# main.net
KiCad netlist of a schematic drawn in EAGLE
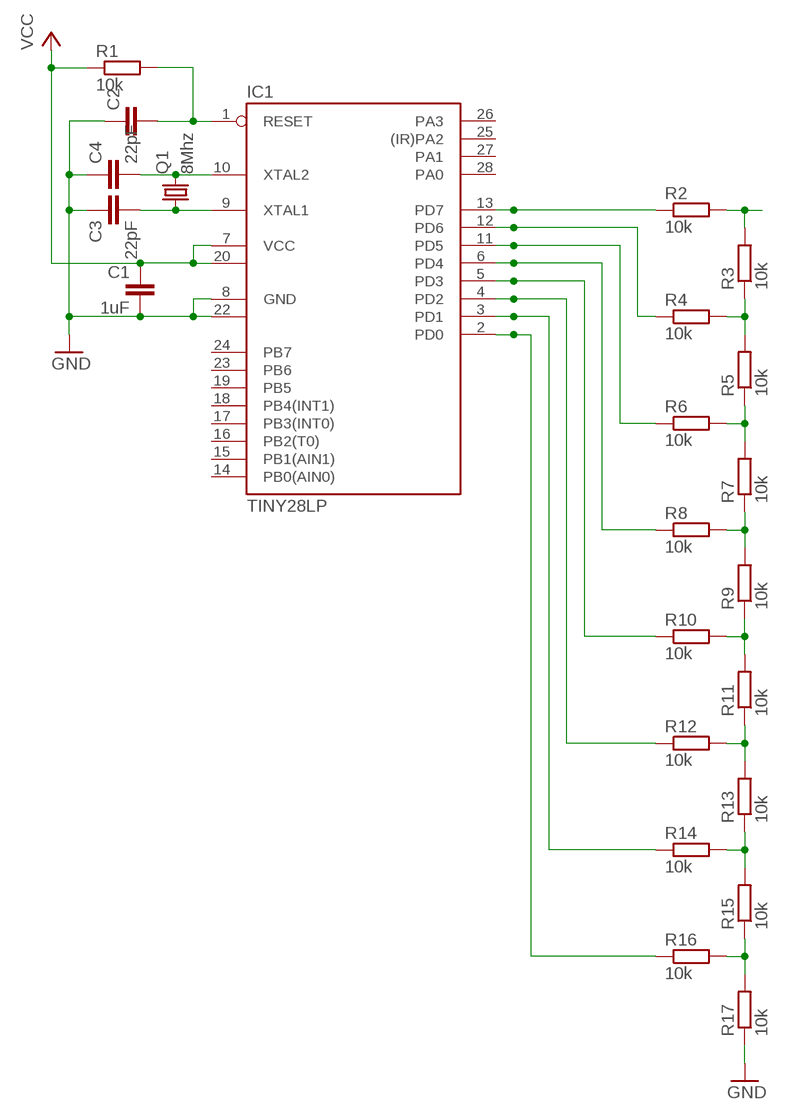
[diagram p0: schematic, sheet 1]

(export (version "E")
  (design (tool "Eeschema 10.0.6"))
  (components
    (comp (ref "C1")
      (value "1uF")
      (footprint "eagle-import:C1206")
      (libsource (lib "eagle-import") (part "C-EUC1206"))
    )
    (comp (ref "C2")
      (value "C-EUC1206")
      (footprint "eagle-import:C1206")
      (libsource (lib "eagle-import") (part "C-EUC1206"))
    )
    (comp (ref "C3")
      (value "22pF")
      (footprint "eagle-import:C1206")
      (libsource (lib "eagle-import") (part "C-EUC1206"))
    )
    (comp (ref "C4")
      (value "22pF")
      (footprint "eagle-import:C1206")
      (libsource (lib "eagle-import") (part "C-EUC1206"))
    )
    (comp (ref "IC1")
      (value "TINY28LP")
      (footprint "eagle-import:DIL28-3")
      (libsource (lib "eagle-import") (part "TINY28PL"))
    )
    (comp (ref "Q1")
      (value "8Mhz")
      (footprint "eagle-import:HC49_S")
      (libsource (lib "eagle-import") (part "CRYSTALHC49S"))
    )
    (comp (ref "R1")
      (value "10k")
      (footprint "eagle-import:R1206")
      (libsource (lib "eagle-import") (part "R-EU_R1206"))
    )
    (comp (ref "R2")
      (value "10k")
      (footprint "eagle-import:R1206")
      (libsource (lib "eagle-import") (part "R-EU_R1206"))
    )
    (comp (ref "R3")
      (value "10k")
      (footprint "eagle-import:R1206")
      (libsource (lib "eagle-import") (part "R-EU_R1206"))
    )
    (comp (ref "R4")
      (value "10k")
      (footprint "eagle-import:R1206")
      (libsource (lib "eagle-import") (part "R-EU_R1206"))
    )
    (comp (ref "R5")
      (value "10k")
      (footprint "eagle-import:R1206")
      (libsource (lib "eagle-import") (part "R-EU_R1206"))
    )
    (comp (ref "R6")
      (value "10k")
      (footprint "eagle-import:R1206")
      (libsource (lib "eagle-import") (part "R-EU_R1206"))
    )
    (comp (ref "R7")
      (value "10k")
      (footprint "eagle-import:R1206")
      (libsource (lib "eagle-import") (part "R-EU_R1206"))
    )
    (comp (ref "R8")
      (value "10k")
      (footprint "eagle-import:R1206")
      (libsource (lib "eagle-import") (part "R-EU_R1206"))
    )
    (comp (ref "R9")
      (value "10k")
      (footprint "eagle-import:R1206")
      (libsource (lib "eagle-import") (part "R-EU_R1206"))
    )
    (comp (ref "R10")
      (value "10k")
      (footprint "eagle-import:R1206")
      (libsource (lib "eagle-import") (part "R-EU_R1206"))
    )
    (comp (ref "R11")
      (value "10k")
      (footprint "eagle-import:R1206")
      (libsource (lib "eagle-import") (part "R-EU_R1206"))
    )
    (comp (ref "R12")
      (value "10k")
      (footprint "eagle-import:R1206")
      (libsource (lib "eagle-import") (part "R-EU_R1206"))
    )
    (comp (ref "R13")
      (value "10k")
      (footprint "eagle-import:R1206")
      (libsource (lib "eagle-import") (part "R-EU_R1206"))
    )
    (comp (ref "R14")
      (value "10k")
      (footprint "eagle-import:R1206")
      (libsource (lib "eagle-import") (part "R-EU_R1206"))
    )
    (comp (ref "R15")
      (value "10k")
      (footprint "eagle-import:R1206")
      (libsource (lib "eagle-import") (part "R-EU_R1206"))
    )
    (comp (ref "R16")
      (value "10k")
      (footprint "eagle-import:R1206")
      (libsource (lib "eagle-import") (part "R-EU_R1206"))
    )
    (comp (ref "R17")
      (value "10k")
      (footprint "eagle-import:R1206")
      (libsource (lib "eagle-import") (part "R-EU_R1206"))
    )
  )
  (nets
    (net (code "1") (name "GND") (class "Default")
      (node (ref "C1") (pin "2") (pinfunction "2_2") (pintype "passive"))
      (node (ref "C2") (pin "1") (pinfunction "1_1") (pintype "passive"))
      (node (ref "C3") (pin "1") (pinfunction "1_1") (pintype "passive"))
      (node (ref "C4") (pin "1") (pinfunction "1_1") (pintype "passive"))
      (node (ref "IC1") (pin "22") (pinfunction "GND1_22") (pintype "power_in"))
      (node (ref "IC1") (pin "8") (pinfunction "GND_8") (pintype "power_in"))
      (node (ref "R17") (pin "1") (pinfunction "1_1") (pintype "passive"))
    )
    (net (code "2") (name "Net-(IC1-PD0)") (class "Default")
      (node (ref "IC1") (pin "2") (pinfunction "PD0_2") (pintype "bidirectional"))
      (node (ref "R16") (pin "1") (pinfunction "1_1") (pintype "passive"))
    )
    (net (code "3") (name "Net-(IC1-PD1)") (class "Default")
      (node (ref "IC1") (pin "3") (pinfunction "PD1_3") (pintype "bidirectional"))
      (node (ref "R14") (pin "1") (pinfunction "1_1") (pintype "passive"))
    )
    (net (code "4") (name "Net-(IC1-PD2)") (class "Default")
      (node (ref "IC1") (pin "4") (pinfunction "PD2_4") (pintype "bidirectional"))
      (node (ref "R12") (pin "1") (pinfunction "1_1") (pintype "passive"))
    )
    (net (code "5") (name "Net-(IC1-PD3)") (class "Default")
      (node (ref "IC1") (pin "5") (pinfunction "PD3_5") (pintype "bidirectional"))
      (node (ref "R10") (pin "1") (pinfunction "1_1") (pintype "passive"))
    )
    (net (code "6") (name "Net-(IC1-PD4)") (class "Default")
      (node (ref "IC1") (pin "6") (pinfunction "PD4_6") (pintype "bidirectional"))
      (node (ref "R8") (pin "1") (pinfunction "1_1") (pintype "passive"))
    )
    (net (code "7") (name "Net-(IC1-PD5)") (class "Default")
      (node (ref "IC1") (pin "11") (pinfunction "PD5_11") (pintype "bidirectional"))
      (node (ref "R6") (pin "1") (pinfunction "1_1") (pintype "passive"))
    )
    (net (code "8") (name "Net-(IC1-PD6)") (class "Default")
      (node (ref "IC1") (pin "12") (pinfunction "PD6_12") (pintype "bidirectional"))
      (node (ref "R4") (pin "1") (pinfunction "1_1") (pintype "passive"))
    )
    (net (code "9") (name "Net-(IC1-PD7)") (class "Default")
      (node (ref "IC1") (pin "13") (pinfunction "PD7_13") (pintype "bidirectional"))
      (node (ref "R2") (pin "1") (pinfunction "1_1") (pintype "passive"))
    )
    (net (code "10") (name "Net-(IC1-RESET)") (class "Default")
      (node (ref "C2") (pin "2") (pinfunction "2_2") (pintype "passive"))
      (node (ref "IC1") (pin "1") (pinfunction "RESET_1") (pintype "input"))
      (node (ref "R1") (pin "2") (pinfunction "2_2") (pintype "passive"))
    )
    (net (code "11") (name "Net-(IC1-XTAL1)") (class "Default")
      (node (ref "C3") (pin "2") (pinfunction "2_2") (pintype "passive"))
      (node (ref "IC1") (pin "9") (pinfunction "XTAL1_9") (pintype "bidirectional"))
      (node (ref "Q1") (pin "1") (pinfunction "1_1") (pintype "passive"))
    )
    (net (code "12") (name "Net-(IC1-XTAL2)") (class "Default")
      (node (ref "C4") (pin "2") (pinfunction "2_2") (pintype "passive"))
      (node (ref "IC1") (pin "10") (pinfunction "XTAL2_10") (pintype "bidirectional"))
      (node (ref "Q1") (pin "2") (pinfunction "2_2") (pintype "passive"))
    )
    (net (code "13") (name "Net-(R2-Pad2)") (class "Default")
      (node (ref "R2") (pin "2") (pinfunction "2_2") (pintype "passive"))
      (node (ref "R3") (pin "2") (pinfunction "2_2") (pintype "passive"))
    )
    (net (code "14") (name "Net-(R3-Pad1)") (class "Default")
      (node (ref "R3") (pin "1") (pinfunction "1_1") (pintype "passive"))
      (node (ref "R4") (pin "2") (pinfunction "2_2") (pintype "passive"))
      (node (ref "R5") (pin "2") (pinfunction "2_2") (pintype "passive"))
    )
    (net (code "15") (name "Net-(R5-Pad1)") (class "Default")
      (node (ref "R5") (pin "1") (pinfunction "1_1") (pintype "passive"))
      (node (ref "R6") (pin "2") (pinfunction "2_2") (pintype "passive"))
      (node (ref "R7") (pin "2") (pinfunction "2_2") (pintype "passive"))
    )
    (net (code "16") (name "Net-(R7-Pad1)") (class "Default")
      (node (ref "R7") (pin "1") (pinfunction "1_1") (pintype "passive"))
      (node (ref "R8") (pin "2") (pinfunction "2_2") (pintype "passive"))
      (node (ref "R9") (pin "2") (pinfunction "2_2") (pintype "passive"))
    )
    (net (code "17") (name "Net-(R10-Pad2)") (class "Default")
      (node (ref "R10") (pin "2") (pinfunction "2_2") (pintype "passive"))
      (node (ref "R11") (pin "2") (pinfunction "2_2") (pintype "passive"))
      (node (ref "R9") (pin "1") (pinfunction "1_1") (pintype "passive"))
    )
    (net (code "18") (name "Net-(R11-Pad1)") (class "Default")
      (node (ref "R11") (pin "1") (pinfunction "1_1") (pintype "passive"))
      (node (ref "R12") (pin "2") (pinfunction "2_2") (pintype "passive"))
      (node (ref "R13") (pin "2") (pinfunction "2_2") (pintype "passive"))
    )
    (net (code "19") (name "Net-(R13-Pad1)") (class "Default")
      (node (ref "R13") (pin "1") (pinfunction "1_1") (pintype "passive"))
      (node (ref "R14") (pin "2") (pinfunction "2_2") (pintype "passive"))
      (node (ref "R15") (pin "2") (pinfunction "2_2") (pintype "passive"))
    )
    (net (code "20") (name "Net-(R15-Pad1)") (class "Default")
      (node (ref "R15") (pin "1") (pinfunction "1_1") (pintype "passive"))
      (node (ref "R16") (pin "2") (pinfunction "2_2") (pintype "passive"))
      (node (ref "R17") (pin "2") (pinfunction "2_2") (pintype "passive"))
    )
    (net (code "21") (name "VCC") (class "Default")
      (node (ref "C1") (pin "1") (pinfunction "1_1") (pintype "passive"))
      (node (ref "IC1") (pin "20") (pinfunction "VCC1_20") (pintype "power_in"))
      (node (ref "IC1") (pin "7") (pinfunction "VCC_7") (pintype "power_in"))
      (node (ref "R1") (pin "1") (pinfunction "1_1") (pintype "passive"))
    )
    (net (code "22") (name "unconnected-(IC1-(IR)PA2-Pad25)") (class "Default")
      (node (ref "IC1") (pin "25") (pinfunction "(IR)PA2_25") (pintype "output"))
    )
    (net (code "23") (name "unconnected-(IC1-NC1-Pad21)") (class "Default")
      (node (ref "IC1") (pin "21") (pinfunction "NC1_21") (pintype "no_connect"))
    )
    (net (code "24") (name "unconnected-(IC1-PA0-Pad28)") (class "Default")
      (node (ref "IC1") (pin "28") (pinfunction "PA0_28") (pintype "bidirectional"))
    )
    (net (code "25") (name "unconnected-(IC1-PA1-Pad27)") (class "Default")
      (node (ref "IC1") (pin "27") (pinfunction "PA1_27") (pintype "bidirectional"))
    )
    (net (code "26") (name "unconnected-(IC1-PA3-Pad26)") (class "Default")
      (node (ref "IC1") (pin "26") (pinfunction "PA3_26") (pintype "bidirectional"))
    )
    (net (code "27") (name "unconnected-(IC1-PB0(AIN0)-Pad14)") (class "Default")
      (node (ref "IC1") (pin "14") (pinfunction "PB0(AIN0)_14") (pintype "input"))
    )
    (net (code "28") (name "unconnected-(IC1-PB1(AIN1)-Pad15)") (class "Default")
      (node (ref "IC1") (pin "15") (pinfunction "PB1(AIN1)_15") (pintype "input"))
    )
    (net (code "29") (name "unconnected-(IC1-PB2(T0)-Pad16)") (class "Default")
      (node (ref "IC1") (pin "16") (pinfunction "PB2(T0)_16") (pintype "input"))
    )
    (net (code "30") (name "unconnected-(IC1-PB3(INT0)-Pad17)") (class "Default")
      (node (ref "IC1") (pin "17") (pinfunction "PB3(INT0)_17") (pintype "input"))
    )
    (net (code "31") (name "unconnected-(IC1-PB4(INT1)-Pad18)") (class "Default")
      (node (ref "IC1") (pin "18") (pinfunction "PB4(INT1)_18") (pintype "input"))
    )
    (net (code "32") (name "unconnected-(IC1-PB5-Pad19)") (class "Default")
      (node (ref "IC1") (pin "19") (pinfunction "PB5_19") (pintype "input"))
    )
    (net (code "33") (name "unconnected-(IC1-PB6-Pad23)") (class "Default")
      (node (ref "IC1") (pin "23") (pinfunction "PB6_23") (pintype "input"))
    )
    (net (code "34") (name "unconnected-(IC1-PB7-Pad24)") (class "Default")
      (node (ref "IC1") (pin "24") (pinfunction "PB7_24") (pintype "input"))
    )
  )
)
